# 1-Schematic_SmartWatch.net
KiCad netlist of a schematic drawn in EasyEDA
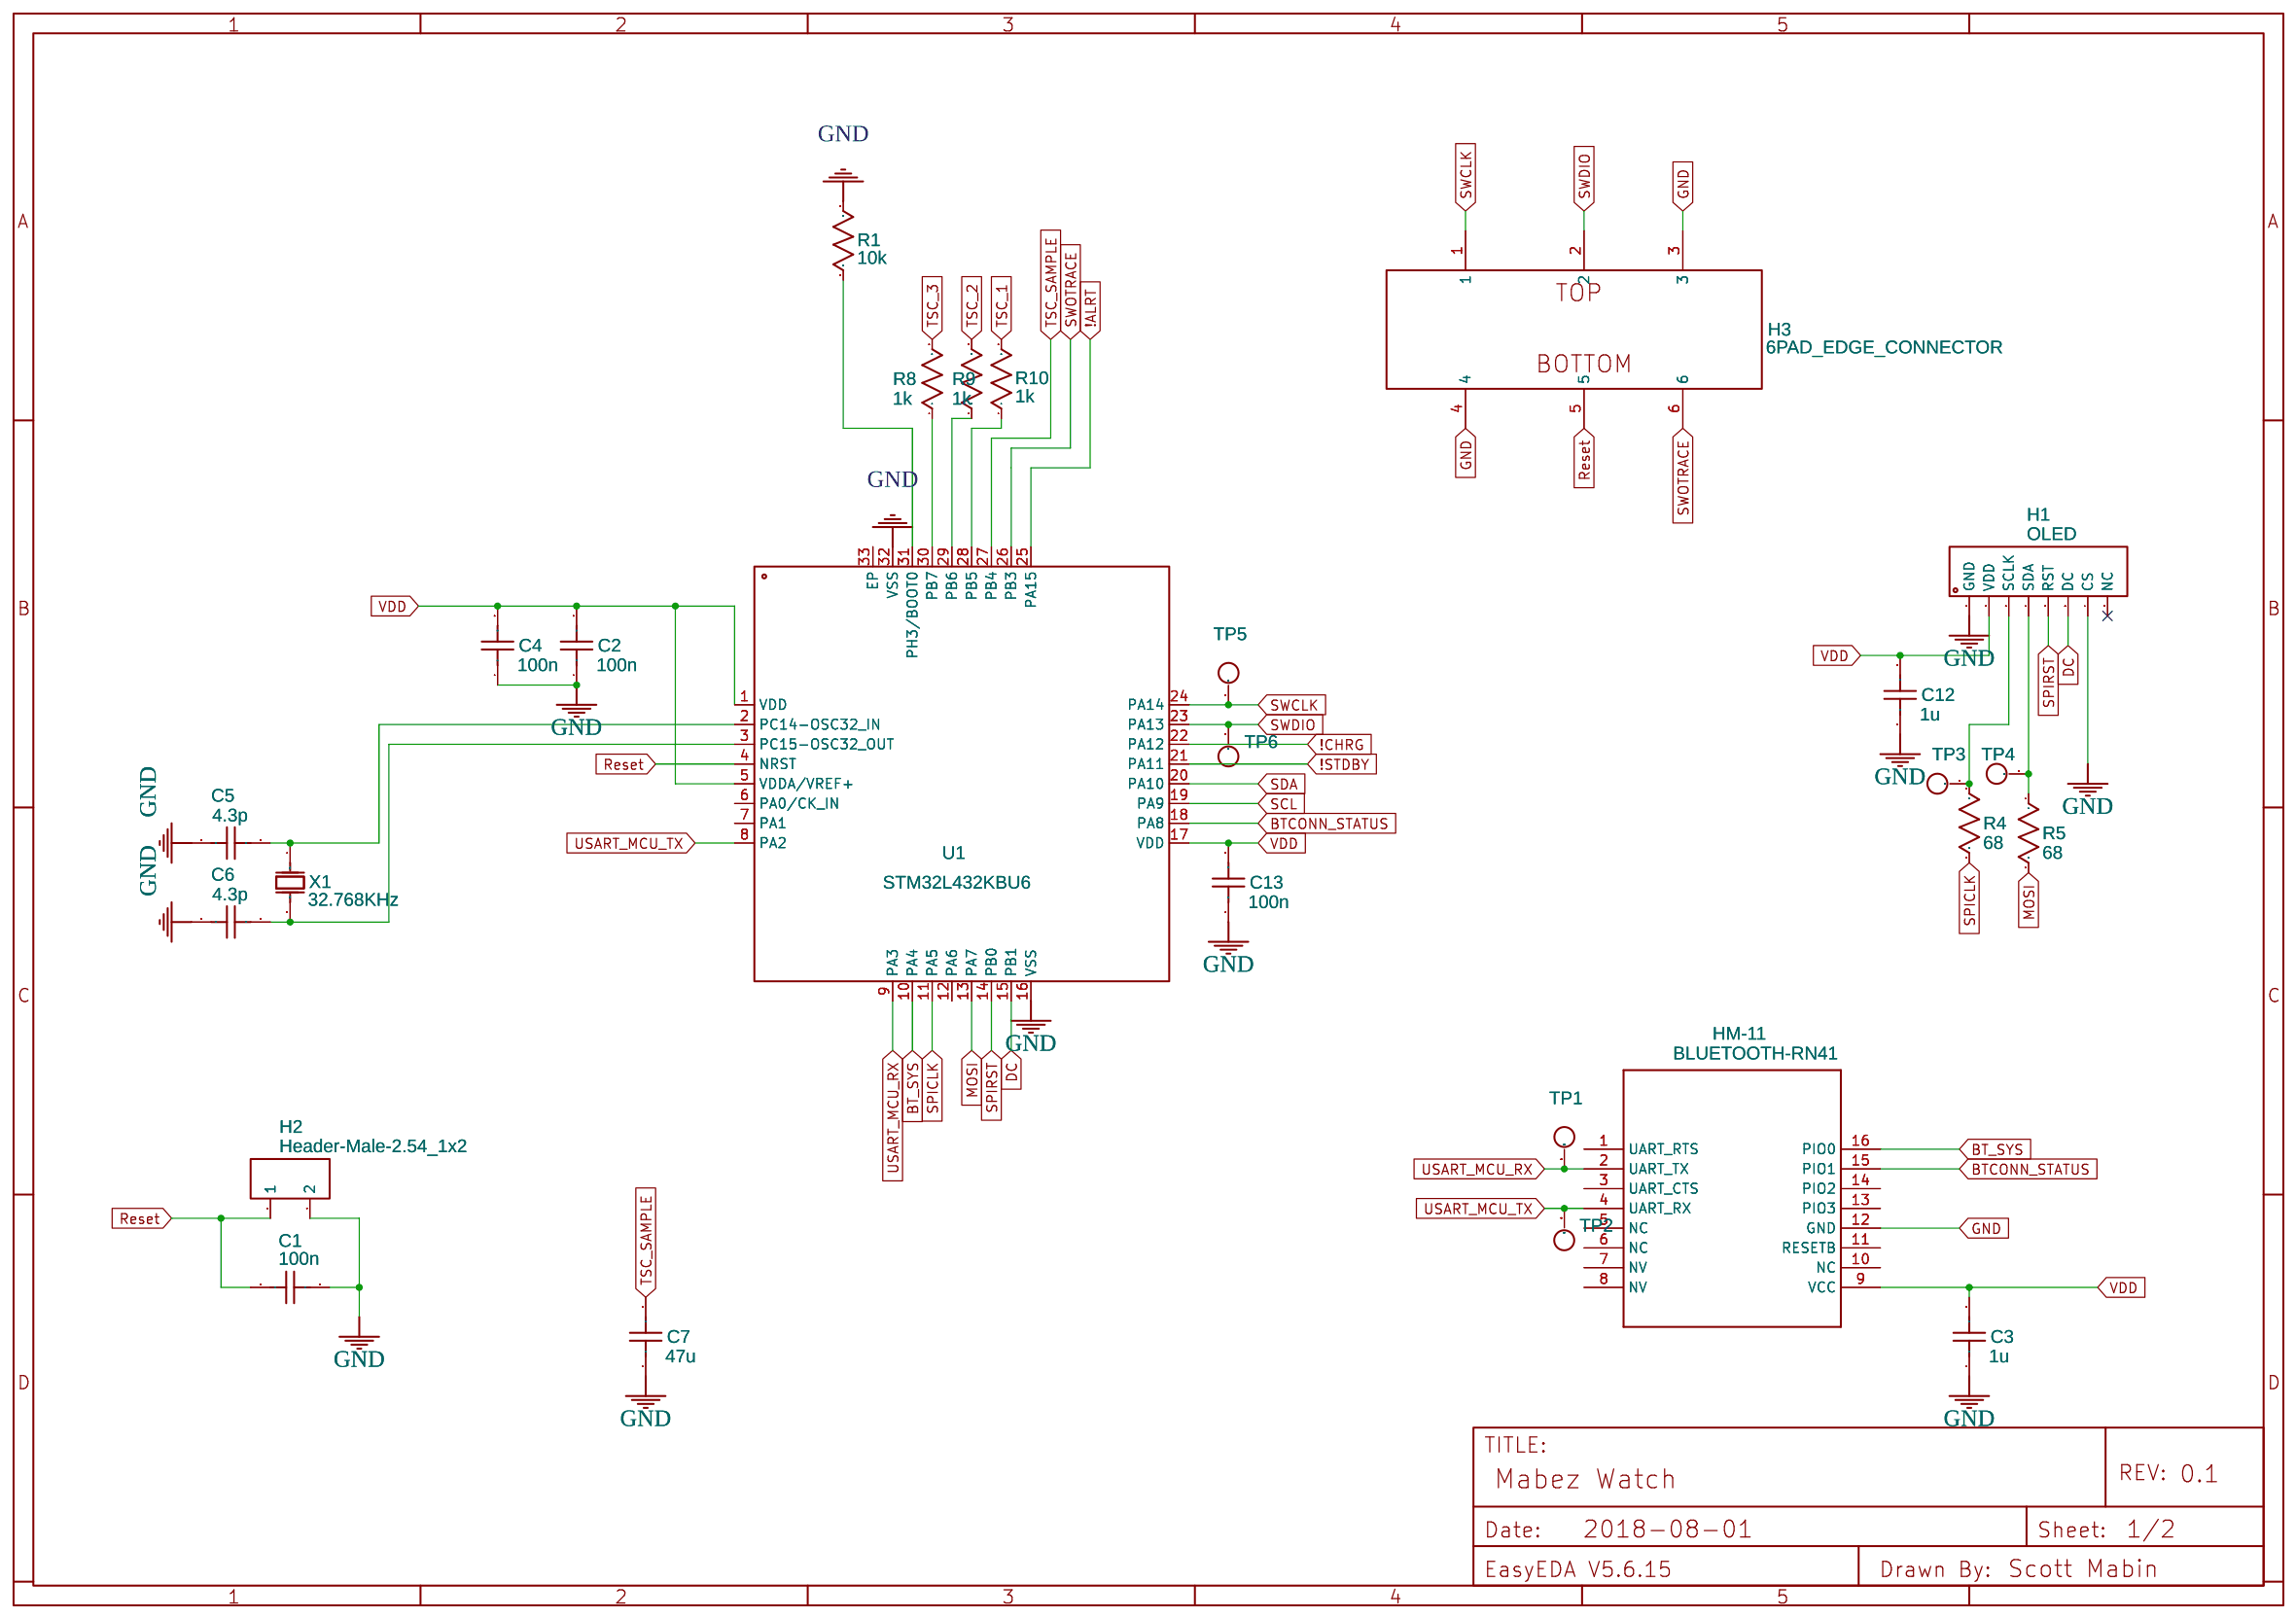
[diagram p0: Main]
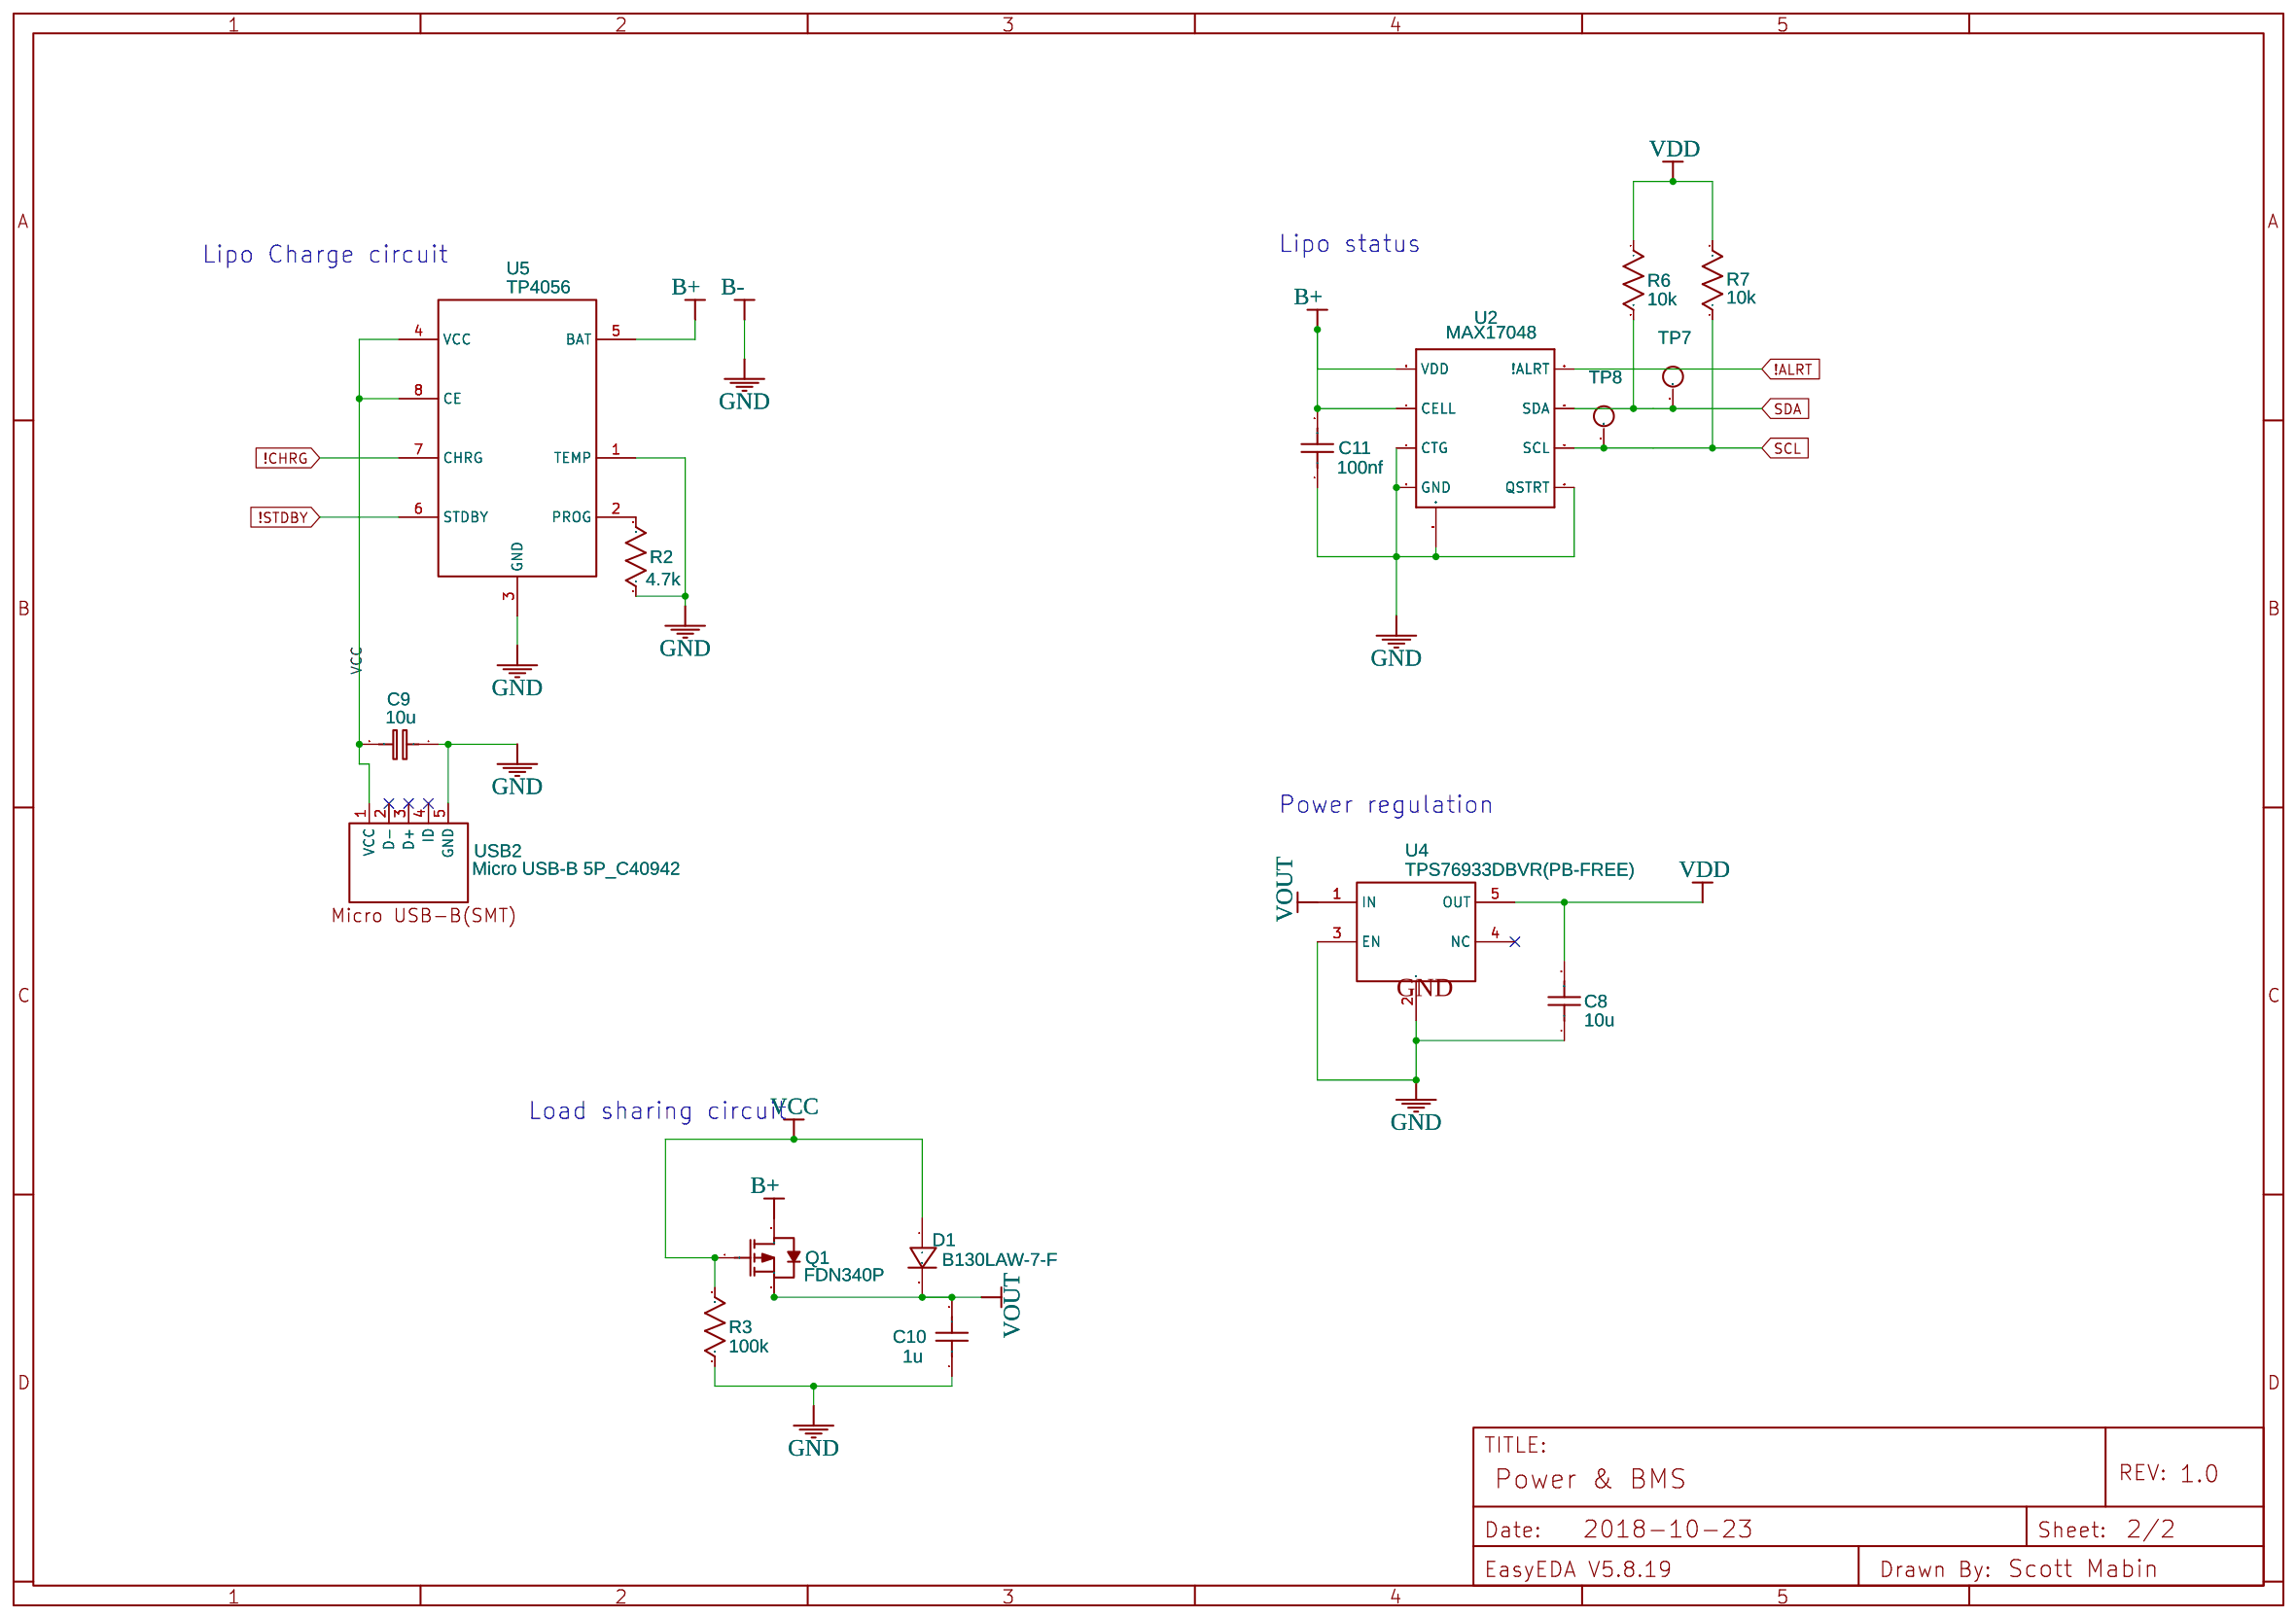
[diagram p1: Power & BMS]

(export (version "E")
  (design (tool "Eeschema 10.0.6"))
  (components
    (comp (ref "C1")
      (value "100n")
      (fields
        (field (name "BOM_Manufacturer Part") "0603B104K101")
        (field (name "BOM_Supplier Part") "C116838")
      )
      (libsource (lib "") (part "Cap_0603_US_1"))
    )
    (comp (ref "C2")
      (value "100n")
      (fields
        (field (name "BOM_Manufacturer Part") "0603B104K101")
        (field (name "BOM_Supplier Part") "C116838")
      )
      (libsource (lib "") (part "Cap_0603_US"))
    )
    (comp (ref "C3")
      (value "1u")
      (fields
        (field (name "BOM_Manufacturer Part") "0603B105K160")
        (field (name "BOM_Supplier Part") "C108463")
      )
      (libsource (lib "") (part "Cap_0603_US"))
    )
    (comp (ref "C4")
      (value "100n")
      (fields
        (field (name "BOM_Manufacturer Part") "0603B104K101")
        (field (name "BOM_Supplier Part") "C116838")
      )
      (libsource (lib "") (part "Cap_0603_US"))
    )
    (comp (ref "C5")
      (value "4.3p")
      (fields
        (field (name "BOM_Manufacturer Part") "0603N4R3B500")
        (field (name "BOM_Supplier Part") "C123576")
      )
      (libsource (lib "") (part "Cap_0603_US_2"))
    )
    (comp (ref "C6")
      (value "4.3p")
      (fields
        (field (name "BOM_Manufacturer Part") "0603N4R3B500")
        (field (name "BOM_Supplier Part") "C123576")
      )
      (libsource (lib "") (part "Cap_0603_US_2"))
    )
    (comp (ref "C7")
      (value "47u")
      (fields
        (field (name "BOM_Manufacturer Part") "0603X476M6R3NT")
        (field (name "BOM_Supplier Part") "C178330")
      )
      (libsource (lib "") (part "Cap_0603_US"))
    )
    (comp (ref "C12")
      (value "1u")
      (fields
        (field (name "BOM_Manufacturer Part") "0603B105K160")
        (field (name "BOM_Supplier Part") "C108463")
      )
      (libsource (lib "") (part "Cap_0603_US"))
    )
    (comp (ref "C13")
      (value "100n")
      (fields
        (field (name "BOM_Manufacturer Part") "0603B104K101")
        (field (name "BOM_Supplier Part") "C116838")
      )
      (libsource (lib "") (part "Cap_0603_US"))
    )
    (comp (ref "H1")
      (value "OLED")
      (fields
        (field (name "BOM_Manufacturer Part") "210S-1*8P L=11.6MMGold-plated black")
        (field (name "BOM_Supplier Part") "C124381")
      )
      (libsource (lib "") (part "Unknown_1025_285"))
    )
    (comp (ref "H2")
      (value "Header-Male-2.54_1x2")
      (fields (field (name "BOM_Manufacturer Part") "826629-2") (field (name "BOM_Supplier Part") "C86471"))
      (libsource (lib "") (part "Unknown_140_590"))
    )
    (comp (ref "H3")
      (value "6PAD_EDGE_CONNECTOR")
      (fields (field (name "BOM_Manufacturer Part") "?") (field (name "BOM_Supplier Part") "undefined"))
      (libsource (lib "") (part "Unknown_795_160"))
    )
    (comp (ref "HM-11")
      (value "BLUETOOTH-RN41")
      (fields (field (name "BOM_Manufacturer Part") "?"))
      (libsource (lib "") (part "Unknown_865_665"))
    )
    (comp (ref "R1")
      (value "10k")
      (fields
        (field (name "BOM_Manufacturer Part") "RN731JTTD1002B25")
        (field (name "BOM_Supplier Part") "C130230")
      )
      (libsource (lib "") (part "Res_0603(1/10W)_US_1"))
    )
    (comp (ref "R4")
      (value "68")
      (fields
        (field (name "BOM_Manufacturer Part") "RCT0368RFLF")
        (field (name "BOM_Supplier Part") "C177541")
      )
      (libsource (lib "") (part "Res_0603(1/10W)_US"))
    )
    (comp (ref "R5")
      (value "68")
      (fields
        (field (name "BOM_Manufacturer Part") "RCT0368RFLF")
        (field (name "BOM_Supplier Part") "C177541")
      )
      (libsource (lib "") (part "Res_0603(1/10W)_US"))
    )
    (comp (ref "R8")
      (value "1k")
      (fields
        (field (name "BOM_Manufacturer Part") "WR06X102JTL")
        (field (name "BOM_Supplier Part") "C163868")
      )
      (libsource (lib "") (part "Res_0603(1/10W)_US_1"))
    )
    (comp (ref "R9")
      (value "1k")
      (fields
        (field (name "BOM_Manufacturer Part") "WR06X102JTL")
        (field (name "BOM_Supplier Part") "C163868")
      )
      (libsource (lib "") (part "Res_0603(1/10W)_US_1"))
    )
    (comp (ref "R10")
      (value "1k")
      (fields
        (field (name "BOM_Manufacturer Part") "WR06X102JTL")
        (field (name "BOM_Supplier Part") "C163868")
      )
      (libsource (lib "") (part "Res_0603(1/10W)_US_1"))
    )
    (comp (ref "TP1")
      (value "TESTPOINTROUND0.5MM")
      (fields (field (name "BOM_Manufacturer Part") "?"))
      (libsource (lib "") (part "Unknown_785_575"))
    )
    (comp (ref "TP2")
      (value "TESTPOINTROUND0.5MM")
      (fields (field (name "BOM_Manufacturer Part") "?"))
      (libsource (lib "") (part "Unknown_785_615"))
    )
    (comp (ref "TP3")
      (value "TESTPOINTROUND0.5MM")
      (fields (field (name "BOM_Manufacturer Part") "?"))
      (libsource (lib "") (part "Unknown_980_390"))
    )
    (comp (ref "TP4")
      (value "TESTPOINTROUND0.5MM")
      (fields (field (name "BOM_Manufacturer Part") "?"))
      (libsource (lib "") (part "Unknown_1010_385"))
    )
    (comp (ref "TP5")
      (value "TESTPOINTROUND0.5MM")
      (fields (field (name "BOM_Manufacturer Part") "?"))
      (libsource (lib "") (part "Unknown_615_340"))
    )
    (comp (ref "TP6")
      (value "TESTPOINTROUND0.5MM")
      (fields (field (name "BOM_Manufacturer Part") "?"))
      (libsource (lib "") (part "Unknown_615_370"))
    )
    (comp (ref "U1")
      (value "STM32L432KBU6")
      (fields (field (name "BOM_Supplier Part") "undefined"))
      (libsource (lib "") (part "Unknown_375_280"))
    )
    (comp (ref "X1")
      (value "32.768KHz")
      (fields
        (field (name "BOM_Manufacturer Part") "NX3215SA 32.768KHZ 12.5PF 20PPM")
        (field (name "BOM_Supplier Part") "C70509")
      )
      (libsource (lib "") (part "NX3215SA 32.768KHZ 12.5PF 20PPM"))
    )
    (comp (ref "C8")
      (value "10u")
      (fields
        (field (name "BOM_Manufacturer Part") "CL10A106MP8NNNC")
        (field (name "BOM_Supplier Part") "C85713")
      )
      (libsource (lib "") (part "Cap_0603_US"))
    )
    (comp (ref "C9")
      (value "10u")
      (fields
        (field (name "BOM_Manufacturer Part") "CL10A106MP8NNNC")
        (field (name "BOM_Supplier Part") "C85713")
      )
      (libsource (lib "") (part "Cap_RAD-0.1_EU"))
    )
    (comp (ref "C10")
      (value "1u")
      (fields
        (field (name "BOM_Manufacturer Part") "0603B105K160")
        (field (name "BOM_Supplier Part") "C108463")
      )
      (libsource (lib "") (part "Cap_0603_US"))
    )
    (comp (ref "C11")
      (value "100nf")
      (fields
        (field (name "BOM_Manufacturer Part") "0603B104K101")
        (field (name "BOM_Supplier Part") "C116838")
      )
      (libsource (lib "") (part "Cap_0603_US"))
    )
    (comp (ref "D1")
      (value "B130LAW-7-F")
      (fields (field (name "BOM_Supplier Part") "C129191"))
      (libsource (lib "") (part "Unknown_460_630"))
    )
    (comp (ref "Q1")
      (value "FDN340P")
      (fields (field (name "BOM_Supplier Part") "C75469"))
      (libsource (lib "") (part "Unknown_385_630"))
    )
    (comp (ref "R2")
      (value "4.7k")
      (fields
        (field (name "BOM_Manufacturer Part") "RS-03K4701FT")
        (field (name "BOM_Supplier Part") "C116693")
      )
      (libsource (lib "") (part "Res_0603(1/10W)_US_1"))
    )
    (comp (ref "R3")
      (value "100k")
      (fields
        (field (name "BOM_Manufacturer Part") "TC0325F1003T5E")
        (field (name "BOM_Supplier Part") "C133733")
      )
      (libsource (lib "") (part "Res_0603(1/10W)_US_1"))
    )
    (comp (ref "R6")
      (value "10k")
      (fields
        (field (name "BOM_Manufacturer Part") "RK73B1JTTD103J")
        (field (name "BOM_Supplier Part") "C159891")
      )
      (libsource (lib "") (part "Res_0603(1/10W)_US"))
    )
    (comp (ref "R7")
      (value "10k")
      (fields
        (field (name "BOM_Manufacturer Part") "RK73B1JTTD103J")
        (field (name "BOM_Supplier Part") "C159891")
      )
      (libsource (lib "") (part "Res_0603(1/10W)_US_1"))
    )
    (comp (ref "TP7")
      (value "TESTPOINTROUND0.5MM")
      (fields (field (name "BOM_Manufacturer Part") "?"))
      (libsource (lib "") (part "Unknown_840_190"))
    )
    (comp (ref "TP8")
      (value "TESTPOINTROUND0.5MM")
      (fields (field (name "BOM_Manufacturer Part") "?"))
      (libsource (lib "") (part "Unknown_805_210"))
    )
    (comp (ref "U2")
      (value "MAX17048")
      (fields (field (name "BOM_Manufacturer Part") "?"))
      (libsource (lib "") (part "Unknown_740_210"))
    )
    (comp (ref "U4")
      (value "TPS76933DBVR(PB-FREE)")
      (fields (field (name "BOM_Supplier Part") "C7101"))
      (libsource (lib "") (part "Unknown_710_470"))
    )
    (comp (ref "U5")
      (value "TP4056")
      (fields (field (name "BOM_Supplier Part") "C16581"))
      (libsource (lib "") (part "Unknown_255_225"))
    )
    (comp (ref "USB2")
      (value "Micro USB-B 5P_C40942")
      (fields (field (name "BOM_Supplier Part") "C40942"))
      (libsource (lib "") (part "Unknown_200_430"))
    )
  )
  (nets
    (net (code "1") (name "!ALRT") (class "Default")
      (node (ref "U1") (pin "25") (pinfunction "PA15_25") (pintype "unspecified"))
      (node (ref "U2") (pin "P$5") (pinfunction "!ALRT_P$5") (pintype "unspecified"))
    )
    (net (code "2") (name "!CHRG") (class "Default")
      (node (ref "U1") (pin "22") (pinfunction "PA12_22") (pintype "unspecified"))
      (node (ref "U5") (pin "7") (pinfunction "CHRG_7") (pintype "unspecified"))
    )
    (net (code "3") (name "!STDBY") (class "Default")
      (node (ref "U1") (pin "21") (pinfunction "PA11_21") (pintype "unspecified"))
      (node (ref "U5") (pin "6") (pinfunction "STDBY_6") (pintype "unspecified"))
    )
    (net (code "4") (name "B+") (class "Default")
      (node (ref "C11") (pin "2") (pinfunction "2_2") (pintype "unspecified"))
      (node (ref "Q1") (pin "3") (pinfunction "D_3") (pintype "unspecified"))
      (node (ref "U2") (pin "P$2") (pinfunction "CELL_P$2") (pintype "input"))
      (node (ref "U2") (pin "P$3") (pinfunction "VDD_P$3") (pintype "unspecified"))
      (node (ref "U5") (pin "5") (pinfunction "BAT_5") (pintype "unspecified"))
    )
    (net (code "5") (name "BTCONN_STATUS") (class "Default")
      (node (ref "HM-11") (pin "15") (pinfunction "PIO1_15") (pintype "unspecified"))
      (node (ref "U1") (pin "18") (pinfunction "PA8_18") (pintype "unspecified"))
    )
    (net (code "6") (name "BT_SYS") (class "Default")
      (node (ref "HM-11") (pin "16") (pinfunction "PIO0_16") (pintype "unspecified"))
      (node (ref "U1") (pin "10") (pinfunction "PA4_10") (pintype "unspecified"))
    )
    (net (code "7") (name "DC") (class "Default")
      (node (ref "H1") (pin "6") (pinfunction "DC_6") (pintype "unspecified"))
      (node (ref "U1") (pin "15") (pinfunction "PB1_15") (pintype "unspecified"))
    )
    (net (code "8") (name "GND") (class "Default")
      (node (ref "C1") (pin "1") (pinfunction "1_1") (pintype "unspecified"))
      (node (ref "C10") (pin "1") (pinfunction "1_1") (pintype "unspecified"))
      (node (ref "C11") (pin "1") (pinfunction "1_1") (pintype "unspecified"))
      (node (ref "C12") (pin "1") (pinfunction "1_1") (pintype "unspecified"))
      (node (ref "C13") (pin "1") (pinfunction "1_1") (pintype "unspecified"))
      (node (ref "C2") (pin "1") (pinfunction "1_1") (pintype "unspecified"))
      (node (ref "C3") (pin "1") (pinfunction "1_1") (pintype "unspecified"))
      (node (ref "C4") (pin "1") (pinfunction "1_1") (pintype "unspecified"))
      (node (ref "C5") (pin "1") (pinfunction "1_1") (pintype "unspecified"))
      (node (ref "C6") (pin "1") (pinfunction "1_1") (pintype "unspecified"))
      (node (ref "C7") (pin "1") (pinfunction "1_1") (pintype "unspecified"))
      (node (ref "C8") (pin "1") (pinfunction "1_1") (pintype "unspecified"))
      (node (ref "C9") (pin "1") (pinfunction "1_1") (pintype "unspecified"))
      (node (ref "H1") (pin "1") (pinfunction "GND_1") (pintype "unspecified"))
      (node (ref "H1") (pin "7") (pinfunction "CS_7") (pintype "unspecified"))
      (node (ref "H2") (pin "2") (pinfunction "2_2") (pintype "unspecified"))
      (node (ref "H3") (pin "3") (pinfunction "3_3") (pintype "unspecified"))
      (node (ref "H3") (pin "4") (pinfunction "4_4") (pintype "unspecified"))
      (node (ref "HM-11") (pin "12") (pinfunction "GND_12") (pintype "unspecified"))
      (node (ref "R1") (pin "2") (pinfunction "2_2") (pintype "unspecified"))
      (node (ref "R2") (pin "1") (pinfunction "1_1") (pintype "unspecified"))
      (node (ref "R3") (pin "1") (pinfunction "1_1") (pintype "unspecified"))
      (node (ref "U1") (pin "16") (pinfunction "VSS_16") (pintype "unspecified"))
      (node (ref "U1") (pin "32") (pinfunction "VSS_32") (pintype "unspecified"))
      (node (ref "U2") (pin "P$1") (pinfunction "CTG_P$1") (pintype "input"))
      (node (ref "U2") (pin "P$4") (pinfunction "GND_P$4") (pintype "unspecified"))
      (node (ref "U2") (pin "P$6") (pinfunction "QSTRT_P$6") (pintype "unspecified"))
      (node (ref "U2") (pin "P$9") (pinfunction "GND_P$9") (pintype "unspecified"))
      (node (ref "U4") (pin "2") (pinfunction "GND_2") (pintype "passive"))
      (node (ref "U4") (pin "3") (pinfunction "EN_3") (pintype "unspecified"))
      (node (ref "U5") (pin "1") (pinfunction "TEMP_1") (pintype "unspecified"))
      (node (ref "U5") (pin "3") (pinfunction "GND_3") (pintype "unspecified"))
      (node (ref "USB2") (pin "5") (pinfunction "GND_5") (pintype "input"))
    )
    (net (code "9") (name "MOSI") (class "Default")
      (node (ref "R5") (pin "2") (pinfunction "2_2") (pintype "unspecified"))
      (node (ref "U1") (pin "13") (pinfunction "PA7_13") (pintype "unspecified"))
    )
    (net (code "10") (name "Net-(H1-SCLK)") (class "Default")
      (node (ref "H1") (pin "3") (pinfunction "SCLK_3") (pintype "unspecified"))
      (node (ref "R4") (pin "1") (pinfunction "1_1") (pintype "unspecified"))
      (node (ref "TP3") (pin "P$1") (pinfunction "P$1_P$1") (pintype "bidirectional"))
    )
    (net (code "11") (name "Net-(H1-SDA)") (class "Default")
      (node (ref "H1") (pin "4") (pinfunction "SDA_4") (pintype "unspecified"))
      (node (ref "R5") (pin "1") (pinfunction "1_1") (pintype "unspecified"))
      (node (ref "TP4") (pin "P$1") (pinfunction "P$1_P$1") (pintype "bidirectional"))
    )
    (net (code "12") (name "Net-(U1-PB5)") (class "Default")
      (node (ref "R10") (pin "1") (pinfunction "1_1") (pintype "unspecified"))
      (node (ref "U1") (pin "28") (pinfunction "PB5_28") (pintype "unspecified"))
    )
    (net (code "13") (name "Net-(U1-PB6)") (class "Default")
      (node (ref "R9") (pin "1") (pinfunction "1_1") (pintype "unspecified"))
      (node (ref "U1") (pin "29") (pinfunction "PB6_29") (pintype "unspecified"))
    )
    (net (code "14") (name "Net-(U1-PB7)") (class "Default")
      (node (ref "R8") (pin "1") (pinfunction "1_1") (pintype "unspecified"))
      (node (ref "U1") (pin "30") (pinfunction "PB7_30") (pintype "unspecified"))
    )
    (net (code "15") (name "Net-(U1-PC14-OSC32_IN)") (class "Default")
      (node (ref "C5") (pin "2") (pinfunction "2_2") (pintype "unspecified"))
      (node (ref "U1") (pin "2") (pinfunction "PC14-OSC32_IN_2") (pintype "unspecified"))
      (node (ref "X1") (pin "1") (pinfunction "OSC1_1") (pintype "input"))
    )
    (net (code "16") (name "Net-(U1-PC15-OSC32_OUT)") (class "Default")
      (node (ref "C6") (pin "2") (pinfunction "2_2") (pintype "unspecified"))
      (node (ref "U1") (pin "3") (pinfunction "PC15-OSC32_OUT_3") (pintype "unspecified"))
      (node (ref "X1") (pin "2") (pinfunction "OSC2_2") (pintype "input"))
    )
    (net (code "17") (name "Net-(U1-PH3{slash}BOOT0)") (class "Default")
      (node (ref "R1") (pin "1") (pinfunction "1_1") (pintype "unspecified"))
      (node (ref "U1") (pin "31") (pinfunction "PH3/BOOT0_31") (pintype "unspecified"))
    )
    (net (code "18") (name "Net-(U5-PROG)") (class "Default")
      (node (ref "R2") (pin "2") (pinfunction "2_2") (pintype "unspecified"))
      (node (ref "U5") (pin "2") (pinfunction "PROG_2") (pintype "unspecified"))
    )
    (net (code "19") (name "Reset") (class "Default")
      (node (ref "C1") (pin "2") (pinfunction "2_2") (pintype "unspecified"))
      (node (ref "H2") (pin "1") (pinfunction "1_1") (pintype "unspecified"))
      (node (ref "H3") (pin "5") (pinfunction "5_5") (pintype "unspecified"))
      (node (ref "U1") (pin "4") (pinfunction "NRST_4") (pintype "unspecified"))
    )
    (net (code "20") (name "SCL") (class "Default")
      (node (ref "R7") (pin "1") (pinfunction "1_1") (pintype "unspecified"))
      (node (ref "TP8") (pin "P$1") (pinfunction "P$1_P$1") (pintype "bidirectional"))
      (node (ref "U1") (pin "19") (pinfunction "PA9_19") (pintype "unspecified"))
      (node (ref "U2") (pin "P$7") (pinfunction "SCL_P$7") (pintype "output"))
    )
    (net (code "21") (name "SDA") (class "Default")
      (node (ref "R6") (pin "2") (pinfunction "2_2") (pintype "unspecified"))
      (node (ref "TP7") (pin "P$1") (pinfunction "P$1_P$1") (pintype "bidirectional"))
      (node (ref "U1") (pin "20") (pinfunction "PA10_20") (pintype "unspecified"))
      (node (ref "U2") (pin "P$8") (pinfunction "SDA_P$8") (pintype "input"))
    )
    (net (code "22") (name "SPICLK") (class "Default")
      (node (ref "R4") (pin "2") (pinfunction "2_2") (pintype "unspecified"))
      (node (ref "U1") (pin "11") (pinfunction "PA5_11") (pintype "unspecified"))
    )
    (net (code "23") (name "SPIRST") (class "Default")
      (node (ref "H1") (pin "5") (pinfunction "RST_5") (pintype "unspecified"))
      (node (ref "U1") (pin "14") (pinfunction "PB0_14") (pintype "unspecified"))
    )
    (net (code "24") (name "SWCLK") (class "Default")
      (node (ref "H3") (pin "1") (pinfunction "1_1") (pintype "unspecified"))
      (node (ref "TP5") (pin "P$1") (pinfunction "P$1_P$1") (pintype "bidirectional"))
      (node (ref "U1") (pin "24") (pinfunction "PA14_24") (pintype "unspecified"))
    )
    (net (code "25") (name "SWDIO") (class "Default")
      (node (ref "H3") (pin "2") (pinfunction "2_2") (pintype "unspecified"))
      (node (ref "TP6") (pin "P$1") (pinfunction "P$1_P$1") (pintype "bidirectional"))
      (node (ref "U1") (pin "23") (pinfunction "PA13_23") (pintype "unspecified"))
    )
    (net (code "26") (name "SWOTRACE") (class "Default")
      (node (ref "H3") (pin "6") (pinfunction "6_6") (pintype "unspecified"))
      (node (ref "U1") (pin "26") (pinfunction "PB3_26") (pintype "unspecified"))
    )
    (net (code "27") (name "TSC_1") (class "Default")
      (node (ref "R10") (pin "2") (pinfunction "2_2") (pintype "unspecified"))
    )
    (net (code "28") (name "TSC_2") (class "Default")
      (node (ref "R9") (pin "2") (pinfunction "2_2") (pintype "unspecified"))
    )
    (net (code "29") (name "TSC_3") (class "Default")
      (node (ref "R8") (pin "2") (pinfunction "2_2") (pintype "unspecified"))
    )
    (net (code "30") (name "TSC_SAMPLE") (class "Default")
      (node (ref "C7") (pin "2") (pinfunction "2_2") (pintype "unspecified"))
      (node (ref "U1") (pin "27") (pinfunction "PB4_27") (pintype "unspecified"))
    )
    (net (code "31") (name "USART_MCU_RX") (class "Default")
      (node (ref "HM-11") (pin "2") (pinfunction "UART_TX_2") (pintype "unspecified"))
      (node (ref "TP1") (pin "P$1") (pinfunction "P$1_P$1") (pintype "bidirectional"))
      (node (ref "U1") (pin "9") (pinfunction "PA3_9") (pintype "unspecified"))
    )
    (net (code "32") (name "USART_MCU_TX") (class "Default")
      (node (ref "HM-11") (pin "4") (pinfunction "UART_RX_4") (pintype "unspecified"))
      (node (ref "TP2") (pin "P$1") (pinfunction "P$1_P$1") (pintype "bidirectional"))
      (node (ref "U1") (pin "8") (pinfunction "PA2_8") (pintype "unspecified"))
    )
    (net (code "33") (name "VCC") (class "Default")
      (node (ref "C9") (pin "2") (pinfunction "2_2") (pintype "unspecified"))
      (node (ref "D1") (pin "1") (pinfunction "1_1") (pintype "unspecified"))
      (node (ref "Q1") (pin "1") (pinfunction "G_1") (pintype "unspecified"))
      (node (ref "R3") (pin "2") (pinfunction "2_2") (pintype "unspecified"))
      (node (ref "U5") (pin "4") (pinfunction "VCC_4") (pintype "unspecified"))
      (node (ref "U5") (pin "8") (pinfunction "CE_8") (pintype "unspecified"))
      (node (ref "USB2") (pin "1") (pinfunction "VCC_1") (pintype "input"))
    )
    (net (code "34") (name "VDD") (class "Default")
      (node (ref "C12") (pin "2") (pinfunction "2_2") (pintype "unspecified"))
      (node (ref "C13") (pin "2") (pinfunction "2_2") (pintype "unspecified"))
      (node (ref "C2") (pin "2") (pinfunction "2_2") (pintype "unspecified"))
      (node (ref "C3") (pin "2") (pinfunction "2_2") (pintype "unspecified"))
      (node (ref "C4") (pin "2") (pinfunction "2_2") (pintype "unspecified"))
      (node (ref "C8") (pin "2") (pinfunction "2_2") (pintype "unspecified"))
      (node (ref "H1") (pin "2") (pinfunction "VDD_2") (pintype "unspecified"))
      (node (ref "HM-11") (pin "9") (pinfunction "VCC_9") (pintype "unspecified"))
      (node (ref "R6") (pin "1") (pinfunction "1_1") (pintype "unspecified"))
      (node (ref "R7") (pin "2") (pinfunction "2_2") (pintype "unspecified"))
      (node (ref "U1") (pin "1") (pinfunction "VDD_1") (pintype "unspecified"))
      (node (ref "U1") (pin "17") (pinfunction "VDD_17") (pintype "unspecified"))
      (node (ref "U1") (pin "5") (pinfunction "VDDA/VREF+_5") (pintype "unspecified"))
      (node (ref "U4") (pin "5") (pinfunction "OUT_5") (pintype "passive"))
    )
    (net (code "35") (name "VOUT") (class "Default")
      (node (ref "C10") (pin "2") (pinfunction "2_2") (pintype "unspecified"))
      (node (ref "D1") (pin "2") (pinfunction "2_2") (pintype "unspecified"))
      (node (ref "Q1") (pin "2") (pinfunction "S_2") (pintype "unspecified"))
      (node (ref "U4") (pin "1") (pinfunction "IN_1") (pintype "passive"))
    )
    (net (code "36") (name "unconnected-(H1-NC-Pad8)") (class "Default")
      (node (ref "H1") (pin "8") (pinfunction "NC_8") (pintype "unspecified+no_connect"))
    )
    (net (code "37") (name "unconnected-(HM-11-NC-Pad5)") (class "Default")
      (node (ref "HM-11") (pin "5") (pinfunction "NC_5") (pintype "unspecified"))
    )
    (net (code "38") (name "unconnected-(HM-11-NC-Pad6)") (class "Default")
      (node (ref "HM-11") (pin "6") (pinfunction "NC_6") (pintype "unspecified"))
    )
    (net (code "39") (name "unconnected-(HM-11-NC-Pad10)") (class "Default")
      (node (ref "HM-11") (pin "10") (pinfunction "NC_10") (pintype "unspecified"))
    )
    (net (code "40") (name "unconnected-(HM-11-NV-Pad7)") (class "Default")
      (node (ref "HM-11") (pin "7") (pinfunction "NV_7") (pintype "unspecified"))
    )
    (net (code "41") (name "unconnected-(HM-11-NV-Pad8)") (class "Default")
      (node (ref "HM-11") (pin "8") (pinfunction "NV_8") (pintype "unspecified"))
    )
    (net (code "42") (name "unconnected-(HM-11-PIO2-Pad14)") (class "Default")
      (node (ref "HM-11") (pin "14") (pinfunction "PIO2_14") (pintype "unspecified"))
    )
    (net (code "43") (name "unconnected-(HM-11-PIO3-Pad13)") (class "Default")
      (node (ref "HM-11") (pin "13") (pinfunction "PIO3_13") (pintype "unspecified"))
    )
    (net (code "44") (name "unconnected-(HM-11-RESETB-Pad11)") (class "Default")
      (node (ref "HM-11") (pin "11") (pinfunction "RESETB_11") (pintype "unspecified"))
    )
    (net (code "45") (name "unconnected-(HM-11-UART_CTS-Pad3)") (class "Default")
      (node (ref "HM-11") (pin "3") (pinfunction "UART_CTS_3") (pintype "unspecified"))
    )
    (net (code "46") (name "unconnected-(HM-11-UART_RTS-Pad1)") (class "Default")
      (node (ref "HM-11") (pin "1") (pinfunction "UART_RTS_1") (pintype "unspecified"))
    )
    (net (code "47") (name "unconnected-(U1-EP-Pad33)") (class "Default")
      (node (ref "U1") (pin "33") (pinfunction "EP_33") (pintype "unspecified"))
    )
    (net (code "48") (name "unconnected-(U1-PA0{slash}CK_IN-Pad6)") (class "Default")
      (node (ref "U1") (pin "6") (pinfunction "PA0/CK_IN_6") (pintype "unspecified"))
    )
    (net (code "49") (name "unconnected-(U1-PA1-Pad7)") (class "Default")
      (node (ref "U1") (pin "7") (pinfunction "PA1_7") (pintype "unspecified"))
    )
    (net (code "50") (name "unconnected-(U1-PA6-Pad12)") (class "Default")
      (node (ref "U1") (pin "12") (pinfunction "PA6_12") (pintype "unspecified"))
    )
    (net (code "51") (name "unconnected-(U4-NC-Pad4)") (class "Default")
      (node (ref "U4") (pin "4") (pinfunction "NC_4") (pintype "unspecified+no_connect"))
    )
    (net (code "52") (name "unconnected-(USB2-D+-Pad3)") (class "Default")
      (node (ref "USB2") (pin "3") (pinfunction "D+_3") (pintype "input+no_connect"))
    )
    (net (code "53") (name "unconnected-(USB2-D--Pad2)") (class "Default")
      (node (ref "USB2") (pin "2") (pinfunction "D-_2") (pintype "input+no_connect"))
    )
    (net (code "54") (name "unconnected-(USB2-ID-Pad4)") (class "Default")
      (node (ref "USB2") (pin "4") (pinfunction "ID_4") (pintype "input+no_connect"))
    )
  )
)
